# Board_Atas.net
KiCad netlist of a schematic drawn in EAGLE
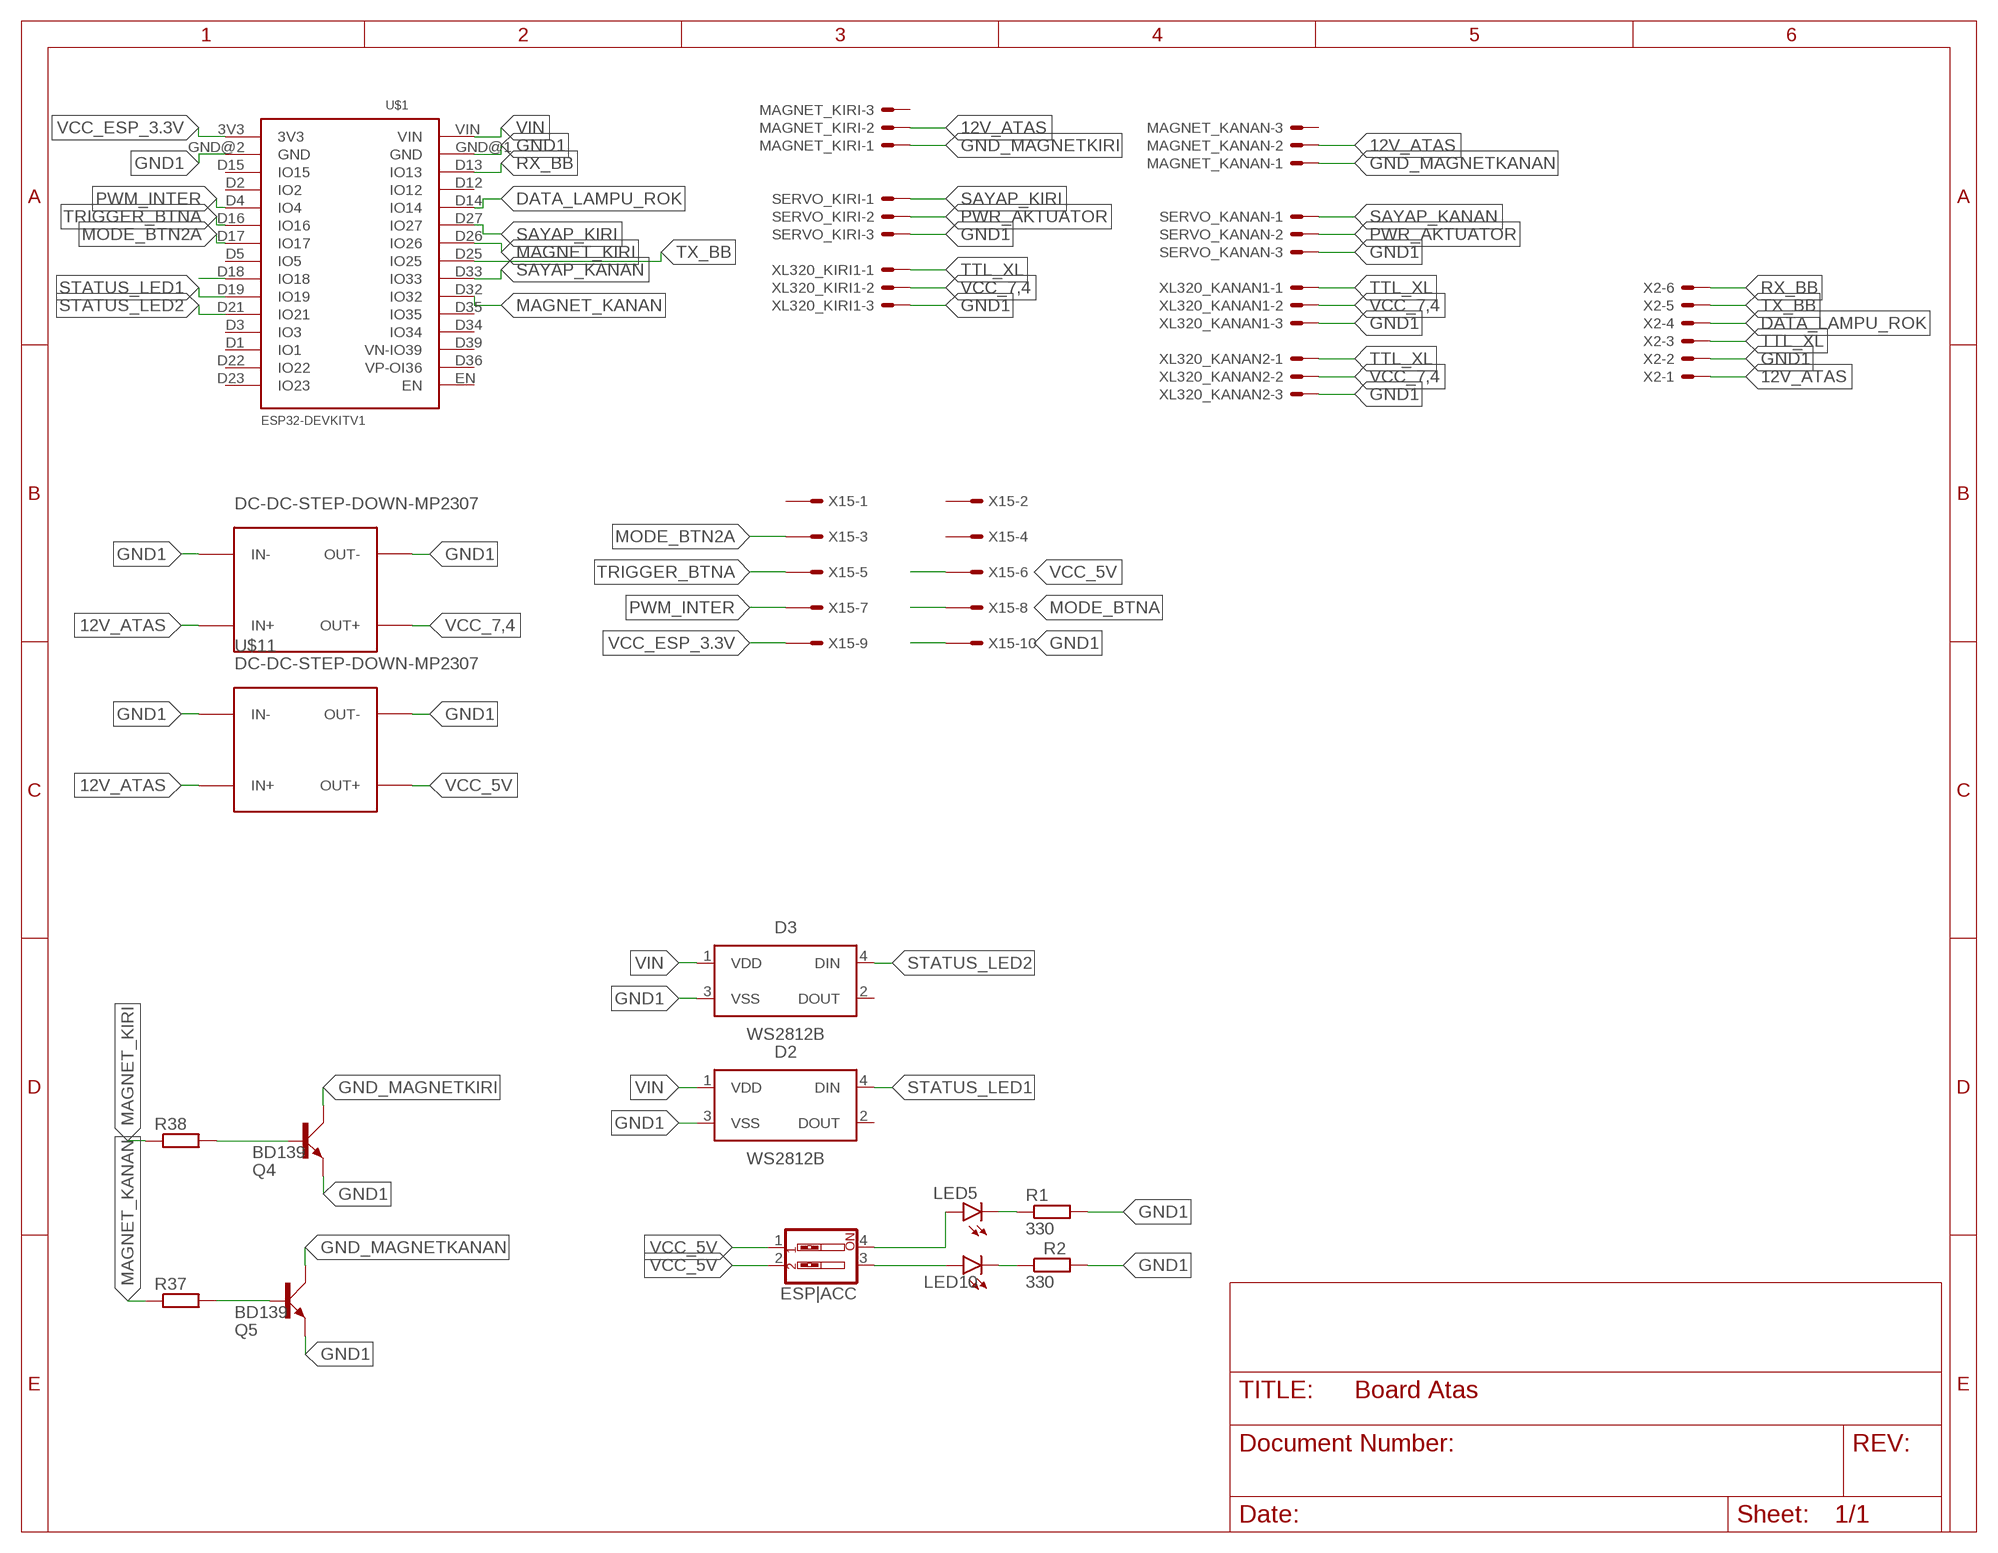
[diagram p0: schematic, sheet 1]

(export (version "E")
  (design (tool "Eeschema 10.0.6"))
  (components
    (comp (ref "D2")
      (value "WS2812B")
      (footprint "eagle-import:WS2812B")
      (fields (field (name "MANUFACTURER") "Worldsemi"))
      (libsource (lib "eagle-import") (part "WS2812B"))
    )
    (comp (ref "D3")
      (value "WS2812B")
      (footprint "eagle-import:WS2812B")
      (fields (field (name "MANUFACTURER") "Worldsemi"))
      (libsource (lib "eagle-import") (part "WS2812B"))
    )
    (comp (ref "ESP|ACC")
      (value "SW_DIP-2")
      (footprint "eagle-import:EDG-02")
      (libsource (lib "eagle-import") (part "SW_DIP-2"))
    )
    (comp (ref "LED5")
      (value "LEDCHIPLED_1206")
      (footprint "eagle-import:CHIPLED_1206")
      (libsource (lib "eagle-import") (part "LEDCHIPLED_1206"))
    )
    (comp (ref "LED10")
      (value "LEDCHIPLED_1206")
      (footprint "eagle-import:CHIPLED_1206")
      (libsource (lib "eagle-import") (part "LEDCHIPLED_1206"))
    )
    (comp (ref "MAGNET_KANAN")
      (value "22-23-2031")
      (footprint "eagle-import:22-23-2031")
      (fields (field (name "MF") "MOLEX"))
      (libsource (lib "eagle-import") (part "22-23-2031"))
    )
    (comp (ref "MAGNET_KIRI")
      (value "22-23-2031")
      (footprint "eagle-import:22-23-2031")
      (fields (field (name "MF") "MOLEX"))
      (libsource (lib "eagle-import") (part "22-23-2031"))
    )
    (comp (ref "Q4")
      (value "BD139")
      (footprint "eagle-import:TO126AV")
      (libsource (lib "eagle-import") (part "BD139"))
    )
    (comp (ref "Q5")
      (value "BD139")
      (footprint "eagle-import:TO126AV")
      (libsource (lib "eagle-import") (part "BD139"))
    )
    (comp (ref "R1")
      (value "330")
      (footprint "eagle-import:M1206")
      (libsource (lib "eagle-import") (part "R-EU_M1206"))
    )
    (comp (ref "R2")
      (value "330")
      (footprint "eagle-import:M1206")
      (libsource (lib "eagle-import") (part "R-EU_M1206"))
    )
    (comp (ref "R37")
      (value "R-EU_M0805")
      (footprint "eagle-import:M0805")
      (libsource (lib "eagle-import") (part "resistor_R-EU_M0805"))
    )
    (comp (ref "R38")
      (value "R-EU_M0805")
      (footprint "eagle-import:M0805")
      (libsource (lib "eagle-import") (part "resistor_R-EU_M0805"))
    )
    (comp (ref "SERVO_KANAN")
      (value "22-23-2031")
      (footprint "eagle-import:22-23-2031")
      (fields (field (name "MF") "MOLEX"))
      (libsource (lib "eagle-import") (part "22-23-2031"))
    )
    (comp (ref "SERVO_KIRI")
      (value "22-23-2031")
      (footprint "eagle-import:22-23-2031")
      (fields (field (name "MF") "MOLEX"))
      (libsource (lib "eagle-import") (part "22-23-2031"))
    )
    (comp (ref "U$1")
      (value "ESP32DEVKITV1")
      (footprint "eagle-import:ESP32-DEVKITV1")
      (libsource (lib "eagle-import") (part "ESP32DEVKITV1"))
    )
    (comp (ref "U$8")
      (value "DC-DC-STEP-DOWN-MP2307")
      (footprint "eagle-import:DC-DC-STEP-DOWN-MP2307")
      (libsource (lib "eagle-import") (part "DC-DC-STEP-DOWN-MP2307"))
    )
    (comp (ref "U$11")
      (value "DC-DC-STEP-DOWN-MP2307")
      (footprint "eagle-import:DC-DC-STEP-DOWN-MP2307")
      (libsource (lib "eagle-import") (part "DC-DC-STEP-DOWN-MP2307"))
    )
    (comp (ref "X2")
      (value "22-23-2061")
      (footprint "eagle-import:22-23-2061")
      (fields (field (name "MF") "MOLEX"))
      (libsource (lib "eagle-import") (part "22-23-2061"))
    )
    (comp (ref "X15")
      (value "057-010-1")
      (footprint "eagle-import:057-010-1")
      (libsource (lib "eagle-import") (part "057-010-1"))
    )
    (comp (ref "XL320_KANAN1")
      (value "22-23-2031")
      (footprint "eagle-import:22-23-2031")
      (fields (field (name "MF") "MOLEX"))
      (libsource (lib "eagle-import") (part "22-23-2031"))
    )
    (comp (ref "XL320_KANAN2")
      (value "22-23-2031")
      (footprint "eagle-import:22-23-2031")
      (fields (field (name "MF") "MOLEX"))
      (libsource (lib "eagle-import") (part "22-23-2031"))
    )
    (comp (ref "XL320_KIRI1")
      (value "22-23-2031")
      (footprint "eagle-import:22-23-2031")
      (fields (field (name "MF") "MOLEX"))
      (libsource (lib "eagle-import") (part "22-23-2031"))
    )
  )
  (nets
    (net (code "1") (name "12V_ATAS") (class "Default")
      (node (ref "MAGNET_KANAN") (pin "2") (pinfunction "S_2") (pintype "passive"))
      (node (ref "MAGNET_KIRI") (pin "2") (pinfunction "S_2") (pintype "passive"))
      (node (ref "U$11") (pin "IN+") (pinfunction "IN+_IN+") (pintype "bidirectional"))
      (node (ref "U$8") (pin "IN+") (pinfunction "IN+_IN+") (pintype "bidirectional"))
      (node (ref "X2") (pin "1") (pinfunction "S_1") (pintype "passive"))
    )
    (net (code "2") (name "DATA_LAMPU_ROK") (class "Default")
      (node (ref "U$1") (pin "D14") (pinfunction "IO14_D14") (pintype "bidirectional"))
      (node (ref "X2") (pin "4") (pinfunction "S_4") (pintype "passive"))
    )
    (net (code "3") (name "GND1") (class "Default")
      (node (ref "D2") (pin "3") (pinfunction "VSS_3") (pintype "power_in"))
      (node (ref "D3") (pin "3") (pinfunction "VSS_3") (pintype "power_in"))
      (node (ref "Q4") (pin "E") (pinfunction "E_E") (pintype "passive"))
      (node (ref "Q5") (pin "E") (pinfunction "E_E") (pintype "passive"))
      (node (ref "R1") (pin "2") (pinfunction "2_2") (pintype "passive"))
      (node (ref "R2") (pin "2") (pinfunction "2_2") (pintype "passive"))
      (node (ref "SERVO_KANAN") (pin "3") (pinfunction "S_3") (pintype "passive"))
      (node (ref "SERVO_KIRI") (pin "3") (pinfunction "S_3") (pintype "passive"))
      (node (ref "U$1") (pin "GND@1") (pinfunction "GND_GND@1") (pintype "bidirectional"))
      (node (ref "U$1") (pin "GND@2") (pinfunction "GND_GND@2") (pintype "bidirectional"))
      (node (ref "U$11") (pin "IN-") (pinfunction "IN-_IN-") (pintype "bidirectional"))
      (node (ref "U$11") (pin "OUT-") (pinfunction "OUT-_OUT-") (pintype "bidirectional"))
      (node (ref "U$8") (pin "IN-") (pinfunction "IN-_IN-") (pintype "bidirectional"))
      (node (ref "U$8") (pin "OUT-") (pinfunction "OUT-_OUT-") (pintype "bidirectional"))
      (node (ref "X15") (pin "10") (pinfunction "S_10") (pintype "passive"))
      (node (ref "X2") (pin "2") (pinfunction "S_2") (pintype "passive"))
      (node (ref "XL320_KANAN1") (pin "3") (pinfunction "S_3") (pintype "passive"))
      (node (ref "XL320_KANAN2") (pin "3") (pinfunction "S_3") (pintype "passive"))
      (node (ref "XL320_KIRI1") (pin "3") (pinfunction "S_3") (pintype "passive"))
    )
    (net (code "4") (name "GND_MAGNETKANAN") (class "Default")
      (node (ref "MAGNET_KANAN") (pin "1") (pinfunction "S_1") (pintype "passive"))
      (node (ref "Q5") (pin "C") (pinfunction "C_C") (pintype "passive"))
    )
    (net (code "5") (name "GND_MAGNETKIRI") (class "Default")
      (node (ref "MAGNET_KIRI") (pin "1") (pinfunction "S_1") (pintype "passive"))
      (node (ref "Q4") (pin "C") (pinfunction "C_C") (pintype "passive"))
    )
    (net (code "6") (name "MAGNET_KANAN") (class "Default")
      (node (ref "R37") (pin "1") (pinfunction "1_1") (pintype "passive"))
      (node (ref "U$1") (pin "D32") (pinfunction "IO32_D32") (pintype "bidirectional"))
    )
    (net (code "7") (name "MAGNET_KIRI") (class "Default")
      (node (ref "R38") (pin "1") (pinfunction "1_1") (pintype "passive"))
      (node (ref "U$1") (pin "D26") (pinfunction "IO26_D26") (pintype "bidirectional"))
    )
    (net (code "8") (name "MODE_BTN2A") (class "Default")
      (node (ref "U$1") (pin "D17") (pinfunction "IO17_D17") (pintype "bidirectional"))
      (node (ref "X15") (pin "3") (pinfunction "S_3") (pintype "passive"))
    )
    (net (code "9") (name "MODE_BTNA") (class "Default")
      (node (ref "U$1") (pin "D18") (pinfunction "IO18_D18") (pintype "bidirectional"))
      (node (ref "X15") (pin "8") (pinfunction "S_8") (pintype "passive"))
    )
    (net (code "10") (name "Net-(LED5-PadC)") (class "Default")
      (node (ref "LED5") (pin "C") (pinfunction "C_C") (pintype "passive"))
      (node (ref "R1") (pin "1") (pinfunction "1_1") (pintype "passive"))
    )
    (net (code "11") (name "Net-(LED10-PadC)") (class "Default")
      (node (ref "LED10") (pin "C") (pinfunction "C_C") (pintype "passive"))
      (node (ref "R2") (pin "1") (pinfunction "1_1") (pintype "passive"))
    )
    (net (code "12") (name "Net-(Q4-PadB)") (class "Default")
      (node (ref "Q4") (pin "B") (pinfunction "B_B") (pintype "passive"))
      (node (ref "R38") (pin "2") (pinfunction "2_2") (pintype "passive"))
    )
    (net (code "13") (name "Net-(Q5-PadB)") (class "Default")
      (node (ref "Q5") (pin "B") (pinfunction "B_B") (pintype "passive"))
      (node (ref "R37") (pin "2") (pinfunction "2_2") (pintype "passive"))
    )
    (net (code "14") (name "PWM_INTER") (class "Default")
      (node (ref "U$1") (pin "D4") (pinfunction "IO4_D4") (pintype "bidirectional"))
      (node (ref "X15") (pin "7") (pinfunction "S_7") (pintype "passive"))
    )
    (net (code "15") (name "PWR_AKTUATOR") (class "Default")
      (node (ref "ESP|ACC") (pin "3") (pinfunction "3_3") (pintype "passive"))
      (node (ref "LED10") (pin "A") (pinfunction "A_A") (pintype "passive"))
      (node (ref "SERVO_KANAN") (pin "2") (pinfunction "S_2") (pintype "passive"))
      (node (ref "SERVO_KIRI") (pin "2") (pinfunction "S_2") (pintype "passive"))
    )
    (net (code "16") (name "RX_BB") (class "Default")
      (node (ref "U$1") (pin "D13") (pinfunction "IO13_D13") (pintype "bidirectional"))
      (node (ref "X2") (pin "6") (pinfunction "S_6") (pintype "passive"))
    )
    (net (code "17") (name "SAYAP_KANAN") (class "Default")
      (node (ref "SERVO_KANAN") (pin "1") (pinfunction "S_1") (pintype "passive"))
      (node (ref "U$1") (pin "D33") (pinfunction "IO33_D33") (pintype "bidirectional"))
    )
    (net (code "18") (name "SAYAP_KIRI") (class "Default")
      (node (ref "SERVO_KIRI") (pin "1") (pinfunction "S_1") (pintype "passive"))
      (node (ref "U$1") (pin "D27") (pinfunction "IO27_D27") (pintype "bidirectional"))
    )
    (net (code "19") (name "STATUS_LED1") (class "Default")
      (node (ref "D2") (pin "4") (pinfunction "DIN_4") (pintype "input"))
      (node (ref "U$1") (pin "D19") (pinfunction "IO19_D19") (pintype "bidirectional"))
    )
    (net (code "20") (name "STATUS_LED2") (class "Default")
      (node (ref "D3") (pin "4") (pinfunction "DIN_4") (pintype "input"))
      (node (ref "U$1") (pin "D21") (pinfunction "IO21_D21") (pintype "bidirectional"))
    )
    (net (code "21") (name "TRIGGER_BTNA") (class "Default")
      (node (ref "U$1") (pin "D16") (pinfunction "IO16_D16") (pintype "bidirectional"))
      (node (ref "X15") (pin "5") (pinfunction "S_5") (pintype "passive"))
    )
    (net (code "22") (name "TTL_XL") (class "Default")
      (node (ref "X2") (pin "3") (pinfunction "S_3") (pintype "passive"))
      (node (ref "XL320_KANAN1") (pin "1") (pinfunction "S_1") (pintype "passive"))
      (node (ref "XL320_KANAN2") (pin "1") (pinfunction "S_1") (pintype "passive"))
      (node (ref "XL320_KIRI1") (pin "1") (pinfunction "S_1") (pintype "passive"))
    )
    (net (code "23") (name "TX_BB") (class "Default")
      (node (ref "U$1") (pin "D25") (pinfunction "IO25_D25") (pintype "bidirectional"))
      (node (ref "X2") (pin "5") (pinfunction "S_5") (pintype "passive"))
    )
    (net (code "24") (name "VCC_5V") (class "Default")
      (node (ref "ESP|ACC") (pin "1") (pinfunction "1_1") (pintype "passive"))
      (node (ref "ESP|ACC") (pin "2") (pinfunction "2_2") (pintype "passive"))
      (node (ref "U$11") (pin "OUT+") (pinfunction "OUT+_OUT+") (pintype "bidirectional"))
      (node (ref "X15") (pin "6") (pinfunction "S_6") (pintype "passive"))
    )
    (net (code "25") (name "VCC_7,4") (class "Default")
      (node (ref "U$8") (pin "OUT+") (pinfunction "OUT+_OUT+") (pintype "bidirectional"))
      (node (ref "XL320_KANAN1") (pin "2") (pinfunction "S_2") (pintype "passive"))
      (node (ref "XL320_KANAN2") (pin "2") (pinfunction "S_2") (pintype "passive"))
      (node (ref "XL320_KIRI1") (pin "2") (pinfunction "S_2") (pintype "passive"))
    )
    (net (code "26") (name "VCC_ESP_3.3V") (class "Default")
      (node (ref "U$1") (pin "3V3") (pinfunction "3V3_3V3") (pintype "bidirectional"))
      (node (ref "X15") (pin "9") (pinfunction "S_9") (pintype "passive"))
    )
    (net (code "27") (name "VIN") (class "Default")
      (node (ref "D2") (pin "1") (pinfunction "VDD_1") (pintype "power_in"))
      (node (ref "D3") (pin "1") (pinfunction "VDD_1") (pintype "power_in"))
      (node (ref "ESP|ACC") (pin "4") (pinfunction "4_4") (pintype "passive"))
      (node (ref "LED5") (pin "A") (pinfunction "A_A") (pintype "passive"))
      (node (ref "U$1") (pin "VIN") (pinfunction "VIN_VIN") (pintype "bidirectional"))
    )
    (net (code "28") (name "unconnected-(D2-DOUT-Pad2)") (class "Default")
      (node (ref "D2") (pin "2") (pinfunction "DOUT_2") (pintype "output"))
    )
    (net (code "29") (name "unconnected-(D3-DOUT-Pad2)") (class "Default")
      (node (ref "D3") (pin "2") (pinfunction "DOUT_2") (pintype "output"))
    )
    (net (code "30") (name "unconnected-(MAGNET_KANANC-S-Pad3)") (class "Default")
      (node (ref "MAGNET_KANAN") (pin "3") (pinfunction "S_3") (pintype "passive"))
    )
    (net (code "31") (name "unconnected-(MAGNET_KIRIC-S-Pad3)") (class "Default")
      (node (ref "MAGNET_KIRI") (pin "3") (pinfunction "S_3") (pintype "passive"))
    )
    (net (code "32") (name "unconnected-(U$1-IO1-PadD1)") (class "Default")
      (node (ref "U$1") (pin "D1") (pinfunction "IO1_D1") (pintype "bidirectional"))
    )
    (net (code "33") (name "unconnected-(U$1-IO2-PadD2)") (class "Default")
      (node (ref "U$1") (pin "D2") (pinfunction "IO2_D2") (pintype "bidirectional"))
    )
    (net (code "34") (name "unconnected-(U$1-IO3-PadD3)") (class "Default")
      (node (ref "U$1") (pin "D3") (pinfunction "IO3_D3") (pintype "bidirectional"))
    )
    (net (code "35") (name "unconnected-(U$1-IO5-PadD5)") (class "Default")
      (node (ref "U$1") (pin "D5") (pinfunction "IO5_D5") (pintype "bidirectional"))
    )
    (net (code "36") (name "unconnected-(U$1-IO12-PadD12)") (class "Default")
      (node (ref "U$1") (pin "D12") (pinfunction "IO12_D12") (pintype "bidirectional"))
    )
    (net (code "37") (name "unconnected-(U$1-IO15-PadD15)") (class "Default")
      (node (ref "U$1") (pin "D15") (pinfunction "IO15_D15") (pintype "bidirectional"))
    )
    (net (code "38") (name "unconnected-(U$1-IO22-PadD22)") (class "Default")
      (node (ref "U$1") (pin "D22") (pinfunction "IO22_D22") (pintype "bidirectional"))
    )
    (net (code "39") (name "unconnected-(U$1-IO23-PadD23)") (class "Default")
      (node (ref "U$1") (pin "D23") (pinfunction "IO23_D23") (pintype "bidirectional"))
    )
    (net (code "40") (name "unconnected-(U$1-IO34-PadD34)") (class "Default")
      (node (ref "U$1") (pin "D34") (pinfunction "IO34_D34") (pintype "bidirectional"))
    )
    (net (code "41") (name "unconnected-(U$1-IO35-PadD35)") (class "Default")
      (node (ref "U$1") (pin "D35") (pinfunction "IO35_D35") (pintype "bidirectional"))
    )
    (net (code "42") (name "unconnected-(U$1-PadEN)") (class "Default")
      (node (ref "U$1") (pin "EN") (pinfunction "EN_EN") (pintype "bidirectional"))
    )
    (net (code "43") (name "unconnected-(U$1-VN-IO39-PadD39)") (class "Default")
      (node (ref "U$1") (pin "D39") (pinfunction "VN-IO39_D39") (pintype "bidirectional"))
    )
    (net (code "44") (name "unconnected-(U$1-VP-OI36-PadD36)") (class "Default")
      (node (ref "U$1") (pin "D36") (pinfunction "VP-OI36_D36") (pintype "bidirectional"))
    )
    (net (code "45") (name "unconnected-(X15A-S-Pad1)") (class "Default")
      (node (ref "X15") (pin "1") (pinfunction "S_1") (pintype "passive"))
    )
    (net (code "46") (name "unconnected-(X15C-S-Pad2)") (class "Default")
      (node (ref "X15") (pin "2") (pinfunction "S_2") (pintype "passive"))
    )
    (net (code "47") (name "unconnected-(X15E-S-Pad4)") (class "Default")
      (node (ref "X15") (pin "4") (pinfunction "S_4") (pintype "passive"))
    )
  )
)
